# ETHERNET.net
KiCad netlist of a schematic drawn in Altium Designer
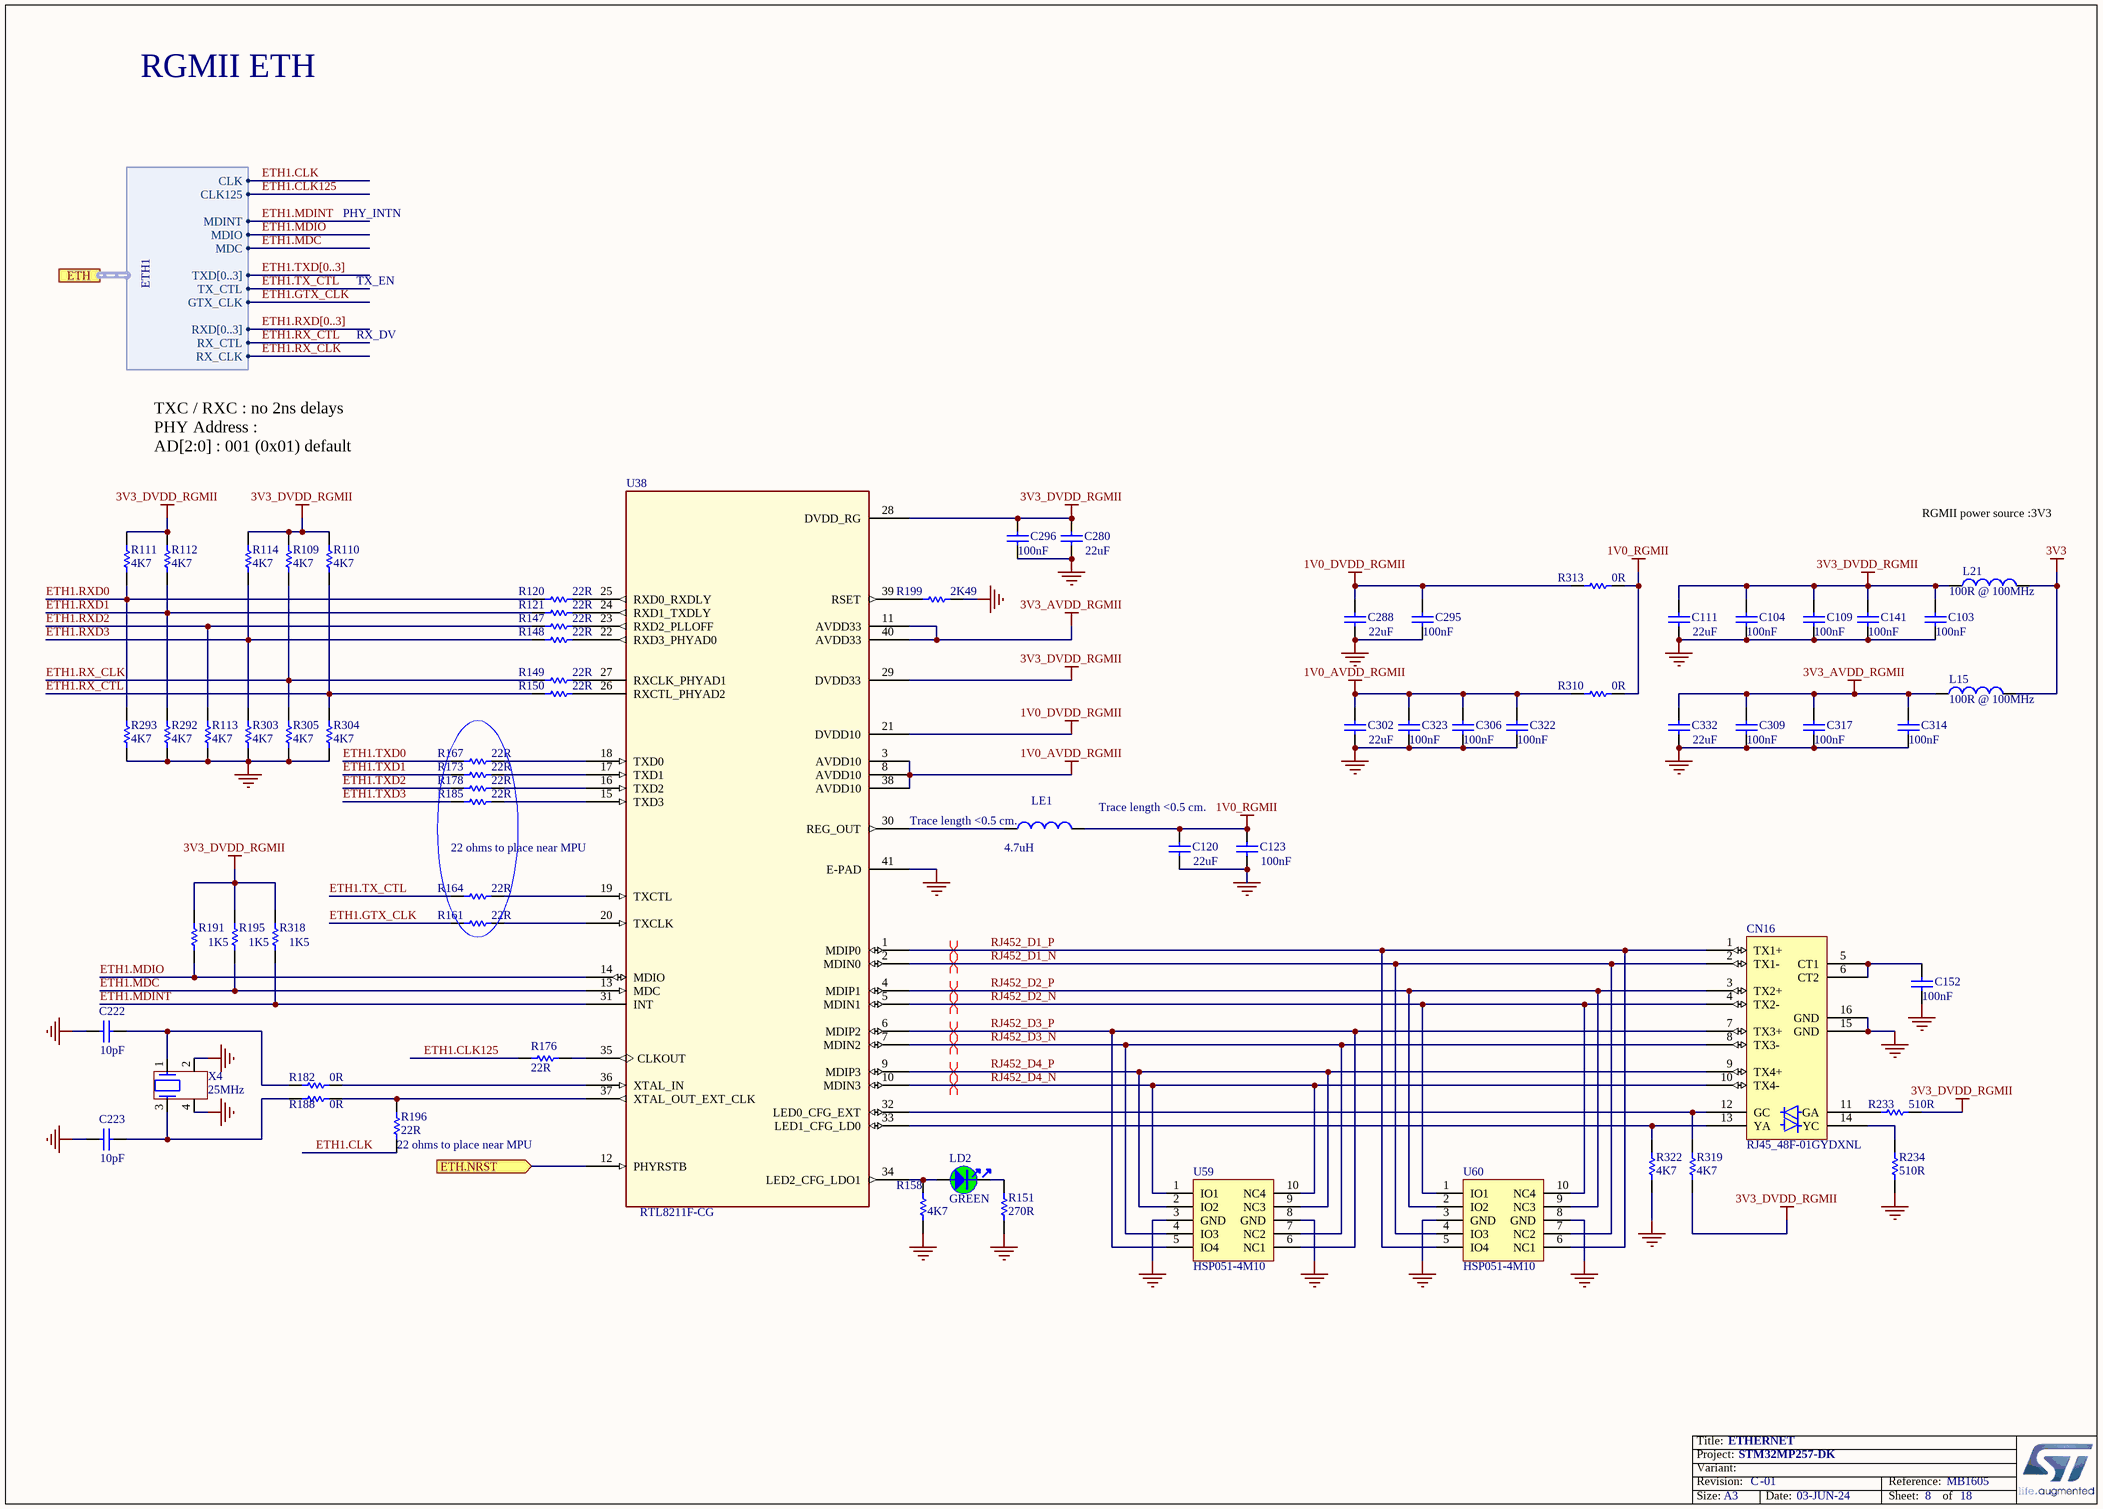
[diagram p0: ETHERNET.SchDoc]

(export (version "E")
  (design (tool "Eeschema 10.0.6"))
  (components
    (comp (ref "C103")
      (value "100nF")
      (footprint "C0402")
      (description "Capacitor,100nF,16V,X7R,10%,0402")
      (fields
        (field (name "INTERNAL_PART_NUMBER") "MCD-00006")
        (field (name "MANUFACTURER_PART_NUMBER") "CC0402KRX7R7BB104")
        (field (name "PROVIDED_BY") "SUBCO")
      )
      (libsource (lib "MCD_PARTS_database") (part "Capacitor"))
    )
    (comp (ref "C104")
      (value "100nF")
      (footprint "C0402")
      (description "Capacitor,100nF,16V,X7R,10%,0402")
      (fields
        (field (name "INTERNAL_PART_NUMBER") "MCD-00006")
        (field (name "MANUFACTURER_PART_NUMBER") "CC0402KRX7R7BB104")
        (field (name "PROVIDED_BY") "SUBCO")
      )
      (libsource (lib "MCD_PARTS_database") (part "Capacitor"))
    )
    (comp (ref "C109")
      (value "100nF")
      (footprint "C0402")
      (description "Capacitor,100nF,16V,X7R,10%,0402")
      (fields
        (field (name "INTERNAL_PART_NUMBER") "MCD-00006")
        (field (name "MANUFACTURER_PART_NUMBER") "CC0402KRX7R7BB104")
        (field (name "PROVIDED_BY") "SUBCO")
      )
      (libsource (lib "MCD_PARTS_database") (part "Capacitor"))
    )
    (comp (ref "C111")
      (value "22uF")
      (footprint "C0603")
      (description "Capacitor,22uF,6V3,X5R,20%,0603")
      (fields
        (field (name "INTERNAL_PART_NUMBER") "MCD-00100")
        (field (name "MANUFACTURER_PART_NUMBER") "GRM188R60J226MEA0J")
        (field (name "PROVIDED_BY") "SUBCO")
      )
      (libsource (lib "MCD_PARTS_database") (part "Capacitor"))
    )
    (comp (ref "C120")
      (value "22uF")
      (footprint "C0603")
      (description "Capacitor,22uF,6V3,X5R,20%,0603")
      (fields
        (field (name "INTERNAL_PART_NUMBER") "MCD-00100")
        (field (name "MANUFACTURER_PART_NUMBER") "GRM188R60J226MEA0J")
        (field (name "PROVIDED_BY") "SUBCO")
      )
      (libsource (lib "MCD_PARTS_database") (part "Capacitor"))
    )
    (comp (ref "C123")
      (value "100nF")
      (footprint "C0402")
      (description "Capacitor,100nF,16V,X7R,10%,0402")
      (fields
        (field (name "INTERNAL_PART_NUMBER") "MCD-00006")
        (field (name "MANUFACTURER_PART_NUMBER") "CC0402KRX7R7BB104")
        (field (name "PROVIDED_BY") "SUBCO")
      )
      (libsource (lib "MCD_PARTS_database") (part "Capacitor"))
    )
    (comp (ref "C141")
      (value "100nF")
      (footprint "C0402")
      (description "Capacitor,100nF,16V,X7R,10%,0402")
      (fields
        (field (name "INTERNAL_PART_NUMBER") "MCD-00006")
        (field (name "MANUFACTURER_PART_NUMBER") "CC0402KRX7R7BB104")
        (field (name "PROVIDED_BY") "SUBCO")
      )
      (libsource (lib "MCD_PARTS_database") (part "Capacitor"))
    )
    (comp (ref "C152")
      (value "100nF")
      (footprint "C0402")
      (description "Capacitor,100nF,16V,X7R,10%,0402")
      (fields
        (field (name "INTERNAL_PART_NUMBER") "MCD-00006")
        (field (name "MANUFACTURER_PART_NUMBER") "CC0402KRX7R7BB104")
        (field (name "PROVIDED_BY") "SUBCO")
      )
      (libsource (lib "MCD_PARTS_database") (part "Capacitor"))
    )
    (comp (ref "C222")
      (value "10pF")
      (footprint "C0402")
      (description "Capacitor,10pF,50V,NPO,5%,0402")
      (fields
        (field (name "INTERNAL_PART_NUMBER") "MCD-00015")
        (field (name "MANUFACTURER_PART_NUMBER") "CC0402JRNPO9BN100")
        (field (name "PROVIDED_BY") "SUBCO")
      )
      (libsource (lib "MCD_PARTS_database") (part "Capacitor"))
    )
    (comp (ref "C223")
      (value "10pF")
      (footprint "C0402")
      (description "Capacitor,10pF,50V,NPO,5%,0402")
      (fields
        (field (name "INTERNAL_PART_NUMBER") "MCD-00015")
        (field (name "MANUFACTURER_PART_NUMBER") "CC0402JRNPO9BN100")
        (field (name "PROVIDED_BY") "SUBCO")
      )
      (libsource (lib "MCD_PARTS_database") (part "Capacitor"))
    )
    (comp (ref "C280")
      (value "22uF")
      (footprint "C0603")
      (description "Capacitor,22uF,6V3,X5R,20%,0603")
      (fields
        (field (name "INTERNAL_PART_NUMBER") "MCD-00100")
        (field (name "MANUFACTURER_PART_NUMBER") "GRM188R60J226MEA0J")
        (field (name "PROVIDED_BY") "SUBCO")
      )
      (libsource (lib "MCD_PARTS_database") (part "Capacitor"))
    )
    (comp (ref "C288")
      (value "22uF")
      (footprint "C0603")
      (description "Capacitor,22uF,6V3,X5R,20%,0603")
      (fields
        (field (name "INTERNAL_PART_NUMBER") "MCD-00100")
        (field (name "MANUFACTURER_PART_NUMBER") "GRM188R60J226MEA0J")
        (field (name "PROVIDED_BY") "SUBCO")
      )
      (libsource (lib "MCD_PARTS_database") (part "Capacitor"))
    )
    (comp (ref "C295")
      (value "100nF")
      (footprint "C0402")
      (description "Capacitor,100nF,16V,X7R,10%,0402")
      (fields
        (field (name "INTERNAL_PART_NUMBER") "MCD-00006")
        (field (name "MANUFACTURER_PART_NUMBER") "CC0402KRX7R7BB104")
        (field (name "PROVIDED_BY") "SUBCO")
      )
      (libsource (lib "MCD_PARTS_database") (part "Capacitor"))
    )
    (comp (ref "C296")
      (value "100nF")
      (footprint "C0402")
      (description "Capacitor,100nF,16V,X7R,10%,0402")
      (fields
        (field (name "INTERNAL_PART_NUMBER") "MCD-00006")
        (field (name "MANUFACTURER_PART_NUMBER") "CC0402KRX7R7BB104")
        (field (name "PROVIDED_BY") "SUBCO")
      )
      (libsource (lib "MCD_PARTS_database") (part "Capacitor"))
    )
    (comp (ref "C302")
      (value "22uF")
      (footprint "C0603")
      (description "Capacitor,22uF,6V3,X5R,20%,0603")
      (fields
        (field (name "INTERNAL_PART_NUMBER") "MCD-00100")
        (field (name "MANUFACTURER_PART_NUMBER") "GRM188R60J226MEA0J")
        (field (name "PROVIDED_BY") "SUBCO")
      )
      (libsource (lib "MCD_PARTS_database") (part "Capacitor"))
    )
    (comp (ref "C306")
      (value "100nF")
      (footprint "C0402")
      (description "Capacitor,100nF,16V,X7R,10%,0402")
      (fields
        (field (name "INTERNAL_PART_NUMBER") "MCD-00006")
        (field (name "MANUFACTURER_PART_NUMBER") "CC0402KRX7R7BB104")
        (field (name "PROVIDED_BY") "SUBCO")
      )
      (libsource (lib "MCD_PARTS_database") (part "Capacitor"))
    )
    (comp (ref "C309")
      (value "100nF")
      (footprint "C0402")
      (description "Capacitor,100nF,16V,X7R,10%,0402")
      (fields
        (field (name "INTERNAL_PART_NUMBER") "MCD-00006")
        (field (name "MANUFACTURER_PART_NUMBER") "CC0402KRX7R7BB104")
        (field (name "PROVIDED_BY") "SUBCO")
      )
      (libsource (lib "MCD_PARTS_database") (part "Capacitor"))
    )
    (comp (ref "C314")
      (value "100nF")
      (footprint "C0402")
      (description "Capacitor,100nF,16V,X7R,10%,0402")
      (fields
        (field (name "INTERNAL_PART_NUMBER") "MCD-00006")
        (field (name "MANUFACTURER_PART_NUMBER") "CC0402KRX7R7BB104")
        (field (name "PROVIDED_BY") "SUBCO")
      )
      (libsource (lib "MCD_PARTS_database") (part "Capacitor"))
    )
    (comp (ref "C317")
      (value "100nF")
      (footprint "C0402")
      (description "Capacitor,100nF,16V,X7R,10%,0402")
      (fields
        (field (name "INTERNAL_PART_NUMBER") "MCD-00006")
        (field (name "MANUFACTURER_PART_NUMBER") "CC0402KRX7R7BB104")
        (field (name "PROVIDED_BY") "SUBCO")
      )
      (libsource (lib "MCD_PARTS_database") (part "Capacitor"))
    )
    (comp (ref "C322")
      (value "100nF")
      (footprint "C0402")
      (description "Capacitor,100nF,16V,X7R,10%,0402")
      (fields
        (field (name "INTERNAL_PART_NUMBER") "MCD-00006")
        (field (name "MANUFACTURER_PART_NUMBER") "CC0402KRX7R7BB104")
        (field (name "PROVIDED_BY") "SUBCO")
      )
      (libsource (lib "MCD_PARTS_database") (part "Capacitor"))
    )
    (comp (ref "C323")
      (value "100nF")
      (footprint "C0402")
      (description "Capacitor,100nF,16V,X7R,10%,0402")
      (fields
        (field (name "INTERNAL_PART_NUMBER") "MCD-00006")
        (field (name "MANUFACTURER_PART_NUMBER") "CC0402KRX7R7BB104")
        (field (name "PROVIDED_BY") "SUBCO")
      )
      (libsource (lib "MCD_PARTS_database") (part "Capacitor"))
    )
    (comp (ref "C332")
      (value "22uF")
      (footprint "C0603")
      (description "Capacitor,22uF,6V3,X5R,20%,0603")
      (fields
        (field (name "INTERNAL_PART_NUMBER") "MCD-00100")
        (field (name "MANUFACTURER_PART_NUMBER") "GRM188R60J226MEA0J")
        (field (name "PROVIDED_BY") "SUBCO")
      )
      (libsource (lib "MCD_PARTS_database") (part "Capacitor"))
    )
    (comp (ref "CN16")
      (value "RJ45_48F-01GYDXNL")
      (footprint "CON_RJ45_YD_48F-01GYDXNL_LED-P")
      (description "Connector_RJ45, led pull down, T= 13.84mm")
      (fields
        (field (name "INTERNAL_PART_NUMBER") "MCD-01129")
        (field (name "MANUFACTURER_PART_NUMBER") "48F-01GYDXNL")
      )
      (libsource (lib "MCD_PARTS_database") (part "RJ45_48F_01GYDXNL_LPD"))
    )
    (comp (ref "L15")
      (value "100R @ 100MHz")
      (footprint "FIL_0603_H0P65")
      (description "Ferrite bead 100R 2A 0603")
      (fields
        (field (name "INTERNAL_PART_NUMBER") "MCD-00094")
        (field (name "MANUFACTURER_PART_NUMBER") "BLM18EG101TN1")
        (field (name "PROVIDED_BY") "SUBCO")
      )
      (libsource (lib "MCD_PARTS_database") (part "BEAD"))
    )
    (comp (ref "L21")
      (value "100R @ 100MHz")
      (footprint "FIL_0603_H0P65")
      (description "Ferrite bead 100R 2A 0603")
      (fields
        (field (name "INTERNAL_PART_NUMBER") "MCD-00094")
        (field (name "MANUFACTURER_PART_NUMBER") "BLM18EG101TN1")
        (field (name "PROVIDED_BY") "SUBCO")
      )
      (libsource (lib "MCD_PARTS_database") (part "BEAD"))
    )
    (comp (ref "LD2")
      (value "GREEN")
      (footprint "LED_0603_OSRAM_LG-Q396-PS-35_GREEN_1A2K_H0P4")
      (description "LED Green, 0603 SMD, Forward Voltage Typ=2V, Max=2.5V")
      (fields
        (field (name "INTERNAL_PART_NUMBER") "MCD-00588")
        (field (name "MANUFACTURER_PART_NUMBER") "LG Q396-PS-35")
        (field (name "PROVIDED_BY") "SUBCO")
      )
      (libsource (lib "MCD_PARTS_database") (part "LED_green"))
    )
    (comp (ref "LE1")
      (value "4.7uH")
      (footprint "L1210_LQH")
      (description "FIXED IND 4.7UH 1A 180 MOHM 30% SMD")
      (fields
        (field (name "INTERNAL_PART_NUMBER") "MCD-00048")
        (field (name "MANUFACTURER_PART_NUMBER") "LQH32PN4R7NN0L")
        (field (name "PROVIDED_BY") "SUBCO")
      )
      (libsource (lib "MCD_PARTS_database") (part "Inductor"))
    )
    (comp (ref "R109")
      (value "4K7")
      (footprint "R0402")
      (description "Resistor,4K7,0402,1%,1/16W")
      (fields
        (field (name "INTERNAL_PART_NUMBER") "MCD-00065")
        (field (name "MANUFACTURER_PART_NUMBER") "RC0402FR-074K7L")
        (field (name "PROVIDED_BY") "SUBCO")
      )
      (libsource (lib "MCD_PARTS_database") (part "Resistor"))
    )
    (comp (ref "R110")
      (value "4K7")
      (footprint "R0402")
      (description "Resistor,4K7,0402,1%,1/16W")
      (fields
        (field (name "INTERNAL_PART_NUMBER") "MCD-00065")
        (field (name "MANUFACTURER_PART_NUMBER") "RC0402FR-074K7L")
        (field (name "PROVIDED_BY") "SUBCO")
      )
      (libsource (lib "MCD_PARTS_database") (part "Resistor"))
    )
    (comp (ref "R111")
      (value "4K7")
      (footprint "R0402")
      (description "Resistor,4K7,0402,1%,1/16W")
      (fields
        (field (name "INTERNAL_PART_NUMBER") "MCD-00065")
        (field (name "MANUFACTURER_PART_NUMBER") "RC0402FR-074K7L")
        (field (name "PROVIDED_BY") "SUBCO")
      )
      (libsource (lib "MCD_PARTS_database") (part "Resistor"))
    )
    (comp (ref "R112")
      (value "4K7")
      (footprint "R0402")
      (description "Resistor,4K7,0402,1%,1/16W")
      (fields
        (field (name "INTERNAL_PART_NUMBER") "MCD-00065")
        (field (name "MANUFACTURER_PART_NUMBER") "RC0402FR-074K7L")
        (field (name "PROVIDED_BY") "SUBCO")
      )
      (libsource (lib "MCD_PARTS_database") (part "Resistor"))
    )
    (comp (ref "R113")
      (value "4K7")
      (footprint "R0402")
      (description "Resistor,4K7,0402,1%,1/16W")
      (fields
        (field (name "INTERNAL_PART_NUMBER") "MCD-00065")
        (field (name "MANUFACTURER_PART_NUMBER") "RC0402FR-074K7L")
        (field (name "PROVIDED_BY") "SUBCO")
      )
      (libsource (lib "MCD_PARTS_database") (part "Resistor"))
    )
    (comp (ref "R114")
      (value "4K7")
      (footprint "R0402")
      (description "Resistor,4K7,0402,1%,1/16W")
      (fields
        (field (name "INTERNAL_PART_NUMBER") "MCD-00065")
        (field (name "MANUFACTURER_PART_NUMBER") "RC0402FR-074K7L")
        (field (name "PROVIDED_BY") "SUBCO")
      )
      (libsource (lib "MCD_PARTS_database") (part "Resistor"))
    )
    (comp (ref "R120")
      (value "22R")
      (footprint "R0201_H0P23")
      (description "Resistor, 22R, 0201, +/-1%, 1/20W")
      (fields
        (field (name "INTERNAL_PART_NUMBER") "MCD-02978")
        (field (name "MANUFACTURER_PART_NUMBER") "RC0201FR-0722RL")
      )
      (libsource (lib "MCD_PARTS_database") (part "Resistor"))
    )
    (comp (ref "R121")
      (value "22R")
      (footprint "R0201_H0P23")
      (description "Resistor, 22R, 0201, +/-1%, 1/20W")
      (fields
        (field (name "INTERNAL_PART_NUMBER") "MCD-02978")
        (field (name "MANUFACTURER_PART_NUMBER") "RC0201FR-0722RL")
      )
      (libsource (lib "MCD_PARTS_database") (part "Resistor"))
    )
    (comp (ref "R147")
      (value "22R")
      (footprint "R0201_H0P23")
      (description "Resistor, 22R, 0201, +/-1%, 1/20W")
      (fields
        (field (name "INTERNAL_PART_NUMBER") "MCD-02978")
        (field (name "MANUFACTURER_PART_NUMBER") "RC0201FR-0722RL")
      )
      (libsource (lib "MCD_PARTS_database") (part "Resistor"))
    )
    (comp (ref "R148")
      (value "22R")
      (footprint "R0201_H0P23")
      (description "Resistor, 22R, 0201, +/-1%, 1/20W")
      (fields
        (field (name "INTERNAL_PART_NUMBER") "MCD-02978")
        (field (name "MANUFACTURER_PART_NUMBER") "RC0201FR-0722RL")
      )
      (libsource (lib "MCD_PARTS_database") (part "Resistor"))
    )
    (comp (ref "R149")
      (value "22R")
      (footprint "R0201_H0P23")
      (description "Resistor, 22R, 0201, +/-1%, 1/20W")
      (fields
        (field (name "INTERNAL_PART_NUMBER") "MCD-02978")
        (field (name "MANUFACTURER_PART_NUMBER") "RC0201FR-0722RL")
      )
      (libsource (lib "MCD_PARTS_database") (part "Resistor"))
    )
    (comp (ref "R150")
      (value "22R")
      (footprint "R0201_H0P23")
      (description "Resistor, 22R, 0201, +/-1%, 1/20W")
      (fields
        (field (name "INTERNAL_PART_NUMBER") "MCD-02978")
        (field (name "MANUFACTURER_PART_NUMBER") "RC0201FR-0722RL")
      )
      (libsource (lib "MCD_PARTS_database") (part "Resistor"))
    )
    (comp (ref "R151")
      (value "270R")
      (footprint "R0402")
      (description "Resistor,270R,0402,1%,1/16W")
      (fields
        (field (name "INTERNAL_PART_NUMBER") "MCD-00441")
        (field (name "MANUFACTURER_PART_NUMBER") "RC0402FR-07270RL")
        (field (name "PROVIDED_BY") "SUBCO")
      )
      (libsource (lib "MCD_PARTS_database") (part "Resistor"))
    )
    (comp (ref "R158")
      (value "4K7")
      (footprint "R0402")
      (description "Resistor,4K7,0402,1%,1/16W")
      (fields
        (field (name "INTERNAL_PART_NUMBER") "MCD-00065")
        (field (name "MANUFACTURER_PART_NUMBER") "RC0402FR-074K7L")
        (field (name "PROVIDED_BY") "SUBCO")
      )
      (libsource (lib "MCD_PARTS_database") (part "Resistor"))
    )
    (comp (ref "R161")
      (value "22R")
      (footprint "R0201_H0P23")
      (description "Resistor, 22R, 0201, +/-1%, 1/20W")
      (fields
        (field (name "INTERNAL_PART_NUMBER") "MCD-02978")
        (field (name "MANUFACTURER_PART_NUMBER") "RC0201FR-0722RL")
      )
      (libsource (lib "MCD_PARTS_database") (part "Resistor"))
    )
    (comp (ref "R164")
      (value "22R")
      (footprint "R0201_H0P23")
      (description "Resistor, 22R, 0201, +/-1%, 1/20W")
      (fields
        (field (name "INTERNAL_PART_NUMBER") "MCD-02978")
        (field (name "MANUFACTURER_PART_NUMBER") "RC0201FR-0722RL")
      )
      (libsource (lib "MCD_PARTS_database") (part "Resistor"))
    )
    (comp (ref "R167")
      (value "22R")
      (footprint "R0201_H0P23")
      (description "Resistor, 22R, 0201, +/-1%, 1/20W")
      (fields
        (field (name "INTERNAL_PART_NUMBER") "MCD-02978")
        (field (name "MANUFACTURER_PART_NUMBER") "RC0201FR-0722RL")
      )
      (libsource (lib "MCD_PARTS_database") (part "Resistor"))
    )
    (comp (ref "R173")
      (value "22R")
      (footprint "R0201_H0P23")
      (description "Resistor, 22R, 0201, +/-1%, 1/20W")
      (fields
        (field (name "INTERNAL_PART_NUMBER") "MCD-02978")
        (field (name "MANUFACTURER_PART_NUMBER") "RC0201FR-0722RL")
      )
      (libsource (lib "MCD_PARTS_database") (part "Resistor"))
    )
    (comp (ref "R176")
      (value "22R")
      (footprint "R0201_H0P23")
      (description "Resistor, 22R, 0201, +/-1%, 1/20W")
      (fields
        (field (name "INTERNAL_PART_NUMBER") "MCD-02978")
        (field (name "MANUFACTURER_PART_NUMBER") "RC0201FR-0722RL")
      )
      (libsource (lib "MCD_PARTS_database") (part "Resistor"))
    )
    (comp (ref "R178")
      (value "22R")
      (footprint "R0201_H0P23")
      (description "Resistor, 22R, 0201, +/-1%, 1/20W")
      (fields
        (field (name "INTERNAL_PART_NUMBER") "MCD-02978")
        (field (name "MANUFACTURER_PART_NUMBER") "RC0201FR-0722RL")
      )
      (libsource (lib "MCD_PARTS_database") (part "Resistor"))
    )
    (comp (ref "R182")
      (value "0R")
      (footprint "R0402")
      (description "Resistor,0R,0402,5%,1/16W")
      (fields
        (field (name "INTERNAL_PART_NUMBER") "MCD-00052")
        (field (name "MANUFACTURER_PART_NUMBER") "RC0402JR-070RL")
        (field (name "PROVIDED_BY") "SUBCO")
      )
      (libsource (lib "MCD_PARTS_database") (part "Resistor"))
    )
    (comp (ref "R185")
      (value "22R")
      (footprint "R0201_H0P23")
      (description "Resistor, 22R, 0201, +/-1%, 1/20W")
      (fields
        (field (name "INTERNAL_PART_NUMBER") "MCD-02978")
        (field (name "MANUFACTURER_PART_NUMBER") "RC0201FR-0722RL")
      )
      (libsource (lib "MCD_PARTS_database") (part "Resistor"))
    )
    (comp (ref "R188")
      (value "0R")
      (footprint "R0402")
      (description "Resistor,0R,0402,5%,1/16W")
      (fields
        (field (name "INTERNAL_PART_NUMBER") "MCD-00052")
        (field (name "MANUFACTURER_PART_NUMBER") "RC0402JR-070RL")
        (field (name "PROVIDED_BY") "SUBCO")
      )
      (libsource (lib "MCD_PARTS_database") (part "Resistor"))
    )
    (comp (ref "R191")
      (value "1K5")
      (footprint "R0402")
      (description "Resistor,1K5,0402,1%,1/16W")
      (fields
        (field (name "INTERNAL_PART_NUMBER") "MCD-00068")
        (field (name "MANUFACTURER_PART_NUMBER") "RC0402FR-071K5L")
        (field (name "PROVIDED_BY") "SUBCO")
      )
      (libsource (lib "MCD_PARTS_database") (part "Resistor"))
    )
    (comp (ref "R195")
      (value "1K5")
      (footprint "R0402")
      (description "Resistor,1K5,0402,1%,1/16W")
      (fields
        (field (name "INTERNAL_PART_NUMBER") "MCD-00068")
        (field (name "MANUFACTURER_PART_NUMBER") "RC0402FR-071K5L")
        (field (name "PROVIDED_BY") "SUBCO")
      )
      (libsource (lib "MCD_PARTS_database") (part "Resistor"))
    )
    (comp (ref "R196")
      (value "22R")
      (footprint "R0201_H0P23")
      (description "Resistor, 22R, 0201, +/-1%, 1/20W")
      (fields
        (field (name "INTERNAL_PART_NUMBER") "MCD-02978")
        (field (name "MANUFACTURER_PART_NUMBER") "RC0201FR-0722RL")
      )
      (libsource (lib "MCD_PARTS_database") (part "Resistor"))
    )
    (comp (ref "R199")
      (value "2K49")
      (footprint "R0402")
      (description "Resistor,2K49,0402,1%,1/16W")
      (fields
        (field (name "INTERNAL_PART_NUMBER") "MCD-00183")
        (field (name "MANUFACTURER_PART_NUMBER") "RC0402FR-072K49L")
        (field (name "PROVIDED_BY") "SUBCO")
      )
      (libsource (lib "MCD_PARTS_database") (part "Resistor"))
    )
    (comp (ref "R233")
      (value "510R")
      (footprint "R0402")
      (description "Resistor,510R,0402,1%,1/16W")
      (fields
        (field (name "INTERNAL_PART_NUMBER") "MCD-00064")
        (field (name "MANUFACTURER_PART_NUMBER") "RC0402FR-07510RL")
        (field (name "PROVIDED_BY") "SUBCO")
      )
      (libsource (lib "MCD_PARTS_database") (part "Resistor"))
    )
    (comp (ref "R234")
      (value "510R")
      (footprint "R0402")
      (description "Resistor,510R,0402,1%,1/16W")
      (fields
        (field (name "INTERNAL_PART_NUMBER") "MCD-00064")
        (field (name "MANUFACTURER_PART_NUMBER") "RC0402FR-07510RL")
        (field (name "PROVIDED_BY") "SUBCO")
      )
      (libsource (lib "MCD_PARTS_database") (part "Resistor"))
    )
    (comp (ref "R292")
      (value "4K7")
      (footprint "R0402")
      (description "Resistor,4K7,0402,1%,1/16W")
      (fields
        (field (name "INTERNAL_PART_NUMBER") "MCD-00065")
        (field (name "MANUFACTURER_PART_NUMBER") "RC0402FR-074K7L")
        (field (name "PROVIDED_BY") "SUBCO")
      )
      (libsource (lib "MCD_PARTS_database") (part "Resistor"))
    )
    (comp (ref "R293")
      (value "4K7")
      (footprint "R0402")
      (description "Resistor,4K7,0402,1%,1/16W")
      (fields
        (field (name "INTERNAL_PART_NUMBER") "MCD-00065")
        (field (name "MANUFACTURER_PART_NUMBER") "RC0402FR-074K7L")
        (field (name "PROVIDED_BY") "SUBCO")
      )
      (libsource (lib "MCD_PARTS_database") (part "Resistor"))
    )
    (comp (ref "R303")
      (value "4K7")
      (footprint "R0402")
      (description "Resistor,4K7,0402,1%,1/16W")
      (fields
        (field (name "INTERNAL_PART_NUMBER") "MCD-00065")
        (field (name "MANUFACTURER_PART_NUMBER") "RC0402FR-074K7L")
        (field (name "PROVIDED_BY") "SUBCO")
      )
      (libsource (lib "MCD_PARTS_database") (part "Resistor"))
    )
    (comp (ref "R304")
      (value "4K7")
      (footprint "R0402")
      (description "Resistor,4K7,0402,1%,1/16W")
      (fields
        (field (name "INTERNAL_PART_NUMBER") "MCD-00065")
        (field (name "MANUFACTURER_PART_NUMBER") "RC0402FR-074K7L")
        (field (name "PROVIDED_BY") "SUBCO")
      )
      (libsource (lib "MCD_PARTS_database") (part "Resistor"))
    )
    (comp (ref "R305")
      (value "4K7")
      (footprint "R0402")
      (description "Resistor,4K7,0402,1%,1/16W")
      (fields
        (field (name "INTERNAL_PART_NUMBER") "MCD-00065")
        (field (name "MANUFACTURER_PART_NUMBER") "RC0402FR-074K7L")
        (field (name "PROVIDED_BY") "SUBCO")
      )
      (libsource (lib "MCD_PARTS_database") (part "Resistor"))
    )
    (comp (ref "R310")
      (value "0R")
      (footprint "R0603")
      (description "Resistor,0R,0603,5%,1/10W")
      (fields
        (field (name "INTERNAL_PART_NUMBER") "MCD-00056")
        (field (name "MANUFACTURER_PART_NUMBER") "RC0603JR-070RL")
        (field (name "PROVIDED_BY") "SUBCO")
      )
      (libsource (lib "MCD_PARTS_database") (part "Resistor"))
    )
    (comp (ref "R313")
      (value "0R")
      (footprint "R0603")
      (description "Resistor,0R,0603,5%,1/10W")
      (fields
        (field (name "INTERNAL_PART_NUMBER") "MCD-00056")
        (field (name "MANUFACTURER_PART_NUMBER") "RC0603JR-070RL")
        (field (name "PROVIDED_BY") "SUBCO")
      )
      (libsource (lib "MCD_PARTS_database") (part "Resistor"))
    )
    (comp (ref "R318")
      (value "1K5")
      (footprint "R0402")
      (description "Resistor,1K5,0402,1%,1/16W")
      (fields
        (field (name "INTERNAL_PART_NUMBER") "MCD-00068")
        (field (name "MANUFACTURER_PART_NUMBER") "RC0402FR-071K5L")
        (field (name "PROVIDED_BY") "SUBCO")
      )
      (libsource (lib "MCD_PARTS_database") (part "Resistor"))
    )
    (comp (ref "R319")
      (value "4K7")
      (footprint "R0402")
      (description "Resistor,4K7,0402,1%,1/16W")
      (fields
        (field (name "INTERNAL_PART_NUMBER") "MCD-00065")
        (field (name "MANUFACTURER_PART_NUMBER") "RC0402FR-074K7L")
        (field (name "PROVIDED_BY") "SUBCO")
      )
      (libsource (lib "MCD_PARTS_database") (part "Resistor"))
    )
    (comp (ref "R322")
      (value "4K7")
      (footprint "R0402")
      (description "Resistor,4K7,0402,1%,1/16W")
      (fields
        (field (name "INTERNAL_PART_NUMBER") "MCD-00065")
        (field (name "MANUFACTURER_PART_NUMBER") "RC0402FR-074K7L")
        (field (name "PROVIDED_BY") "SUBCO")
      )
      (libsource (lib "MCD_PARTS_database") (part "Resistor"))
    )
    (comp (ref "U38")
      (value "RTL8211F-CG")
      (footprint "ICC_QFN40-EPAD_5X5_P040")
      (description "10/100/1000M GIGABIT Ethernet Transceiver, QFN40 , SMPS version")
      (fields
        (field (name "INTERNAL_PART_NUMBER") "MCD-01130")
        (field (name "MANUFACTURER") "REALTEK")
        (field (name "PROVIDED_BY") "SUBCO")
      )
      (libsource (lib "MCD_PARTS_database") (part "RTL8211F-CG"))
    )
    (comp (ref "U59")
      (value "HSP051-4M10")
      (footprint "ESD_UQFN-10L_2P5X1_P050")
      (description "4-line ESD protection for high speed lines")
      (fields (field (name "INTERNAL_PART_NUMBER") "MCD-00667") (field (name "BMS_PART_NUMBER") "9179041"))
      (libsource (lib "MCD_PARTS_database") (part "HSP051-4M10"))
    )
    (comp (ref "U60")
      (value "HSP051-4M10")
      (footprint "ESD_UQFN-10L_2P5X1_P050")
      (description "4-line ESD protection for high speed lines")
      (fields (field (name "INTERNAL_PART_NUMBER") "MCD-00667") (field (name "BMS_PART_NUMBER") "9179041"))
      (libsource (lib "MCD_PARTS_database") (part "HSP051-4M10"))
    )
    (comp (ref "X4")
      (value "25MHz")
      (footprint "CRY_NX3225HA_4P")
      (description "Crystal 25Mhz, 10pF, -+50PPM, SMD")
      (fields
        (field (name "INTERNAL_PART_NUMBER") "MCD-01463")
        (field (name "MANUFACTURER_PART_NUMBER") "NX3225GA-25MHZ-EXS00A-CG06750")
        (field (name "PROVIDED_BY") "SUBCO")
      )
      (libsource (lib "MCD_PARTS_database") (part "XTAL_4_PINS"))
    )
  )
  (nets
    (net (code "2") (name "/ETH.NRST") (class "Default")
      (node (ref "U38") (pin "12") (pinfunction "PHYRSTB_12") (pintype "input"))
    )
    (net (code "3") (name "/ETH1.CLK") (class "Default")
      (node (ref "R196") (pin "1") (pinfunction "1_1") (pintype "passive"))
    )
    (net (code "4") (name "/ETH1.CLK125") (class "Default")
      (node (ref "R176") (pin "1") (pinfunction "1_1") (pintype "passive"))
    )
    (net (code "5") (name "/ETH1.GTX_CLK") (class "Default")
      (node (ref "R161") (pin "1") (pinfunction "1_1") (pintype "passive"))
    )
    (net (code "6") (name "/ETH1.MDC") (class "Default")
      (node (ref "R195") (pin "1") (pinfunction "1_1") (pintype "passive"))
      (node (ref "U38") (pin "13") (pinfunction "MDC_13") (pintype "input"))
    )
    (net (code "7") (name "/ETH1.MDINT") (class "Default")
      (node (ref "R318") (pin "1") (pinfunction "1_1") (pintype "passive"))
      (node (ref "U38") (pin "31") (pinfunction "INT_31") (pintype "passive"))
    )
    (net (code "8") (name "/ETH1.MDIO") (class "Default")
      (node (ref "R191") (pin "1") (pinfunction "1_1") (pintype "passive"))
      (node (ref "U38") (pin "14") (pinfunction "MDIO_14") (pintype "bidirectional"))
    )
    (net (code "9") (name "/ETH1.RXD0") (class "Default")
      (node (ref "R111") (pin "1") (pinfunction "1_1") (pintype "passive"))
      (node (ref "R120") (pin "1") (pinfunction "1_1") (pintype "passive"))
      (node (ref "R293") (pin "2") (pinfunction "2_2") (pintype "passive"))
    )
    (net (code "10") (name "/ETH1.RXD1") (class "Default")
      (node (ref "R112") (pin "1") (pinfunction "1_1") (pintype "passive"))
      (node (ref "R121") (pin "1") (pinfunction "1_1") (pintype "passive"))
      (node (ref "R292") (pin "2") (pinfunction "2_2") (pintype "passive"))
    )
    (net (code "11") (name "/ETH1.RXD2") (class "Default")
      (node (ref "R113") (pin "2") (pinfunction "2_2") (pintype "passive"))
      (node (ref "R147") (pin "1") (pinfunction "1_1") (pintype "passive"))
    )
    (net (code "12") (name "/ETH1.RXD3") (class "Default")
      (node (ref "R114") (pin "1") (pinfunction "1_1") (pintype "passive"))
      (node (ref "R148") (pin "1") (pinfunction "1_1") (pintype "passive"))
      (node (ref "R303") (pin "2") (pinfunction "2_2") (pintype "passive"))
    )
    (net (code "14") (name "/ETH1.RX_CLK") (class "Default")
      (node (ref "R109") (pin "1") (pinfunction "1_1") (pintype "passive"))
      (node (ref "R149") (pin "1") (pinfunction "1_1") (pintype "passive"))
      (node (ref "R305") (pin "2") (pinfunction "2_2") (pintype "passive"))
    )
    (net (code "15") (name "/ETH1.RX_CTL") (class "Default")
      (node (ref "R110") (pin "1") (pinfunction "1_1") (pintype "passive"))
      (node (ref "R150") (pin "1") (pinfunction "1_1") (pintype "passive"))
      (node (ref "R304") (pin "2") (pinfunction "2_2") (pintype "passive"))
    )
    (net (code "16") (name "/ETH1.TXD0") (class "Default")
      (node (ref "R167") (pin "1") (pinfunction "1_1") (pintype "passive"))
    )
    (net (code "17") (name "/ETH1.TXD1") (class "Default")
      (node (ref "R173") (pin "1") (pinfunction "1_1") (pintype "passive"))
    )
    (net (code "18") (name "/ETH1.TXD2") (class "Default")
      (node (ref "R178") (pin "1") (pinfunction "1_1") (pintype "passive"))
    )
    (net (code "19") (name "/ETH1.TXD3") (class "Default")
      (node (ref "R185") (pin "1") (pinfunction "1_1") (pintype "passive"))
    )
    (net (code "21") (name "/ETH1.TX_CTL") (class "Default")
      (node (ref "R164") (pin "1") (pinfunction "1_1") (pintype "passive"))
    )
    (net (code "22") (name "/RJ452_D1_N") (class "Default")
      (node (ref "CN16") (pin "2") (pinfunction "TX1-_2") (pintype "bidirectional"))
      (node (ref "U38") (pin "2") (pinfunction "MDIN0_2") (pintype "bidirectional"))
      (node (ref "U60") (pin "4") (pinfunction "IO3_4") (pintype "passive"))
      (node (ref "U60") (pin "7") (pinfunction "NC2_7") (pintype "passive"))
    )
    (net (code "23") (name "/RJ452_D1_P") (class "Default")
      (node (ref "CN16") (pin "1") (pinfunction "TX1+_1") (pintype "bidirectional"))
      (node (ref "U38") (pin "1") (pinfunction "MDIP0_1") (pintype "bidirectional"))
      (node (ref "U60") (pin "5") (pinfunction "IO4_5") (pintype "passive"))
      (node (ref "U60") (pin "6") (pinfunction "NC1_6") (pintype "passive"))
    )
    (net (code "24") (name "/RJ452_D2_N") (class "Default")
      (node (ref "CN16") (pin "4") (pinfunction "TX2-_4") (pintype "bidirectional"))
      (node (ref "U38") (pin "5") (pinfunction "MDIN1_5") (pintype "bidirectional"))
      (node (ref "U60") (pin "1") (pinfunction "IO1_1") (pintype "passive"))
      (node (ref "U60") (pin "10") (pinfunction "NC4_10") (pintype "passive"))
    )
    (net (code "25") (name "/RJ452_D2_P") (class "Default")
      (node (ref "CN16") (pin "3") (pinfunction "TX2+_3") (pintype "bidirectional"))
      (node (ref "U38") (pin "4") (pinfunction "MDIP1_4") (pintype "bidirectional"))
      (node (ref "U60") (pin "2") (pinfunction "IO2_2") (pintype "passive"))
      (node (ref "U60") (pin "9") (pinfunction "NC3_9") (pintype "passive"))
    )
    (net (code "26") (name "/RJ452_D3_N") (class "Default")
      (node (ref "CN16") (pin "8") (pinfunction "TX3-_8") (pintype "bidirectional"))
      (node (ref "U38") (pin "7") (pinfunction "MDIN2_7") (pintype "bidirectional"))
      (node (ref "U59") (pin "4") (pinfunction "IO3_4") (pintype "passive"))
      (node (ref "U59") (pin "7") (pinfunction "NC2_7") (pintype "passive"))
    )
    (net (code "27") (name "/RJ452_D3_P") (class "Default")
      (node (ref "CN16") (pin "7") (pinfunction "TX3+_7") (pintype "bidirectional"))
      (node (ref "U38") (pin "6") (pinfunction "MDIP2_6") (pintype "bidirectional"))
      (node (ref "U59") (pin "5") (pinfunction "IO4_5") (pintype "passive"))
      (node (ref "U59") (pin "6") (pinfunction "NC1_6") (pintype "passive"))
    )
    (net (code "28") (name "/RJ452_D4_N") (class "Default")
      (node (ref "CN16") (pin "10") (pinfunction "TX4-_10") (pintype "bidirectional"))
      (node (ref "U38") (pin "10") (pinfunction "MDIN3_10") (pintype "bidirectional"))
      (node (ref "U59") (pin "1") (pinfunction "IO1_1") (pintype "passive"))
      (node (ref "U59") (pin "10") (pinfunction "NC4_10") (pintype "passive"))
    )
    (net (code "29") (name "/RJ452_D4_P") (class "Default")
      (node (ref "CN16") (pin "9") (pinfunction "TX4+_9") (pintype "bidirectional"))
      (node (ref "U38") (pin "9") (pinfunction "MDIP3_9") (pintype "bidirectional"))
      (node (ref "U59") (pin "2") (pinfunction "IO2_2") (pintype "passive"))
      (node (ref "U59") (pin "9") (pinfunction "NC3_9") (pintype "passive"))
    )
    (net (code "31") (name "1V0_AVDD_RGMII") (class "Default")
      (node (ref "C302") (pin "2") (pinfunction "2_2") (pintype "passive"))
      (node (ref "C306") (pin "2") (pinfunction "2_2") (pintype "passive"))
      (node (ref "C322") (pin "2") (pinfunction "2_2") (pintype "passive"))
      (node (ref "C323") (pin "2") (pinfunction "2_2") (pintype "passive"))
      (node (ref "R310") (pin "1") (pinfunction "1_1") (pintype "passive"))
      (node (ref "U38") (pin "3") (pinfunction "AVDD10_3") (pintype "power_in"))
      (node (ref "U38") (pin "38") (pinfunction "AVDD10_38") (pintype "power_in"))
      (node (ref "U38") (pin "8") (pinfunction "AVDD10_8") (pintype "power_in"))
    )
    (net (code "32") (name "1V0_DVDD_RGMII") (class "Default")
      (node (ref "C288") (pin "2") (pinfunction "2_2") (pintype "passive"))
      (node (ref "C295") (pin "2") (pinfunction "2_2") (pintype "passive"))
      (node (ref "R313") (pin "1") (pinfunction "1_1") (pintype "passive"))
      (node (ref "U38") (pin "21") (pinfunction "DVDD10_21") (pintype "power_in"))
    )
    (net (code "33") (name "1V0_RGMII") (class "Default")
      (node (ref "C120") (pin "2") (pinfunction "2_2") (pintype "passive"))
      (node (ref "C123") (pin "2") (pinfunction "2_2") (pintype "passive"))
      (node (ref "LE1") (pin "2") (pinfunction "2_2") (pintype "passive"))
      (node (ref "R310") (pin "2") (pinfunction "2_2") (pintype "passive"))
      (node (ref "R313") (pin "2") (pinfunction "2_2") (pintype "passive"))
    )
    (net (code "34") (name "3V3") (class "Default")
      (node (ref "L15") (pin "2") (pinfunction "2_2") (pintype "passive"))
      (node (ref "L21") (pin "2") (pinfunction "2_2") (pintype "passive"))
    )
    (net (code "35") (name "3V3_AVDD_RGMII") (class "Default")
      (node (ref "C309") (pin "2") (pinfunction "2_2") (pintype "passive"))
      (node (ref "C314") (pin "2") (pinfunction "2_2") (pintype "passive"))
      (node (ref "C317") (pin "2") (pinfunction "2_2") (pintype "passive"))
      (node (ref "C332") (pin "2") (pinfunction "2_2") (pintype "passive"))
      (node (ref "L15") (pin "1") (pinfunction "1_1") (pintype "passive"))
      (node (ref "U38") (pin "11") (pinfunction "AVDD33_11") (pintype "power_in"))
      (node (ref "U38") (pin "40") (pinfunction "AVDD33_40") (pintype "power_in"))
    )
    (net (code "36") (name "3V3_DVDD_RGMII") (class "Default")
      (node (ref "C103") (pin "2") (pinfunction "2_2") (pintype "passive"))
      (node (ref "C104") (pin "2") (pinfunction "2_2") (pintype "passive"))
      (node (ref "C109") (pin "2") (pinfunction "2_2") (pintype "passive"))
      (node (ref "C111") (pin "2") (pinfunction "2_2") (pintype "passive"))
      (node (ref "C141") (pin "2") (pinfunction "2_2") (pintype "passive"))
      (node (ref "C280") (pin "1") (pinfunction "1_1") (pintype "passive"))
      (node (ref "C296") (pin "2") (pinfunction "2_2") (pintype "passive"))
      (node (ref "L21") (pin "1") (pinfunction "1_1") (pintype "passive"))
      (node (ref "R109") (pin "2") (pinfunction "2_2") (pintype "passive"))
      (node (ref "R110") (pin "2") (pinfunction "2_2") (pintype "passive"))
      (node (ref "R111") (pin "2") (pinfunction "2_2") (pintype "passive"))
      (node (ref "R112") (pin "2") (pinfunction "2_2") (pintype "passive"))
      (node (ref "R114") (pin "2") (pinfunction "2_2") (pintype "passive"))
      (node (ref "R191") (pin "2") (pinfunction "2_2") (pintype "passive"))
      (node (ref "R195") (pin "2") (pinfunction "2_2") (pintype "passive"))
      (node (ref "R233") (pin "2") (pinfunction "2_2") (pintype "passive"))
      (node (ref "R318") (pin "2") (pinfunction "2_2") (pintype "passive"))
      (node (ref "R319") (pin "1") (pinfunction "1_1") (pintype "passive"))
      (node (ref "U38") (pin "28") (pinfunction "DVDD_RG_28") (pintype "power_in"))
      (node (ref "U38") (pin "29") (pinfunction "DVDD33_29") (pintype "power_in"))
    )
    (net (code "37") (name "GND") (class "Default")
      (node (ref "C103") (pin "1") (pinfunction "1_1") (pintype "passive"))
      (node (ref "C104") (pin "1") (pinfunction "1_1") (pintype "passive"))
      (node (ref "C109") (pin "1") (pinfunction "1_1") (pintype "passive"))
      (node (ref "C111") (pin "1") (pinfunction "1_1") (pintype "passive"))
      (node (ref "C120") (pin "1") (pinfunction "1_1") (pintype "passive"))
      (node (ref "C123") (pin "1") (pinfunction "1_1") (pintype "passive"))
      (node (ref "C141") (pin "1") (pinfunction "1_1") (pintype "passive"))
      (node (ref "C152") (pin "1") (pinfunction "1_1") (pintype "passive"))
      (node (ref "C222") (pin "1") (pinfunction "1_1") (pintype "passive"))
      (node (ref "C223") (pin "1") (pinfunction "1_1") (pintype "passive"))
      (node (ref "C280") (pin "2") (pinfunction "2_2") (pintype "passive"))
      (node (ref "C288") (pin "1") (pinfunction "1_1") (pintype "passive"))
      (node (ref "C295") (pin "1") (pinfunction "1_1") (pintype "passive"))
      (node (ref "C296") (pin "1") (pinfunction "1_1") (pintype "passive"))
      (node (ref "C302") (pin "1") (pinfunction "1_1") (pintype "passive"))
      (node (ref "C306") (pin "1") (pinfunction "1_1") (pintype "passive"))
      (node (ref "C309") (pin "1") (pinfunction "1_1") (pintype "passive"))
      (node (ref "C314") (pin "1") (pinfunction "1_1") (pintype "passive"))
      (node (ref "C317") (pin "1") (pinfunction "1_1") (pintype "passive"))
      (node (ref "C322") (pin "1") (pinfunction "1_1") (pintype "passive"))
      (node (ref "C323") (pin "1") (pinfunction "1_1") (pintype "passive"))
      (node (ref "C332") (pin "1") (pinfunction "1_1") (pintype "passive"))
      (node (ref "CN16") (pin "15") (pinfunction "GND_15") (pintype "power_in"))
      (node (ref "CN16") (pin "16") (pinfunction "GND_16") (pintype "power_in"))
      (node (ref "R113") (pin "1") (pinfunction "1_1") (pintype "passive"))
      (node (ref "R151") (pin "2") (pinfunction "2_2") (pintype "passive"))
      (node (ref "R158") (pin "1") (pinfunction "1_1") (pintype "passive"))
      (node (ref "R199") (pin "2") (pinfunction "2_2") (pintype "passive"))
      (node (ref "R234") (pin "1") (pinfunction "1_1") (pintype "passive"))
      (node (ref "R292") (pin "1") (pinfunction "1_1") (pintype "passive"))
      (node (ref "R293") (pin "1") (pinfunction "1_1") (pintype "passive"))
      (node (ref "R303") (pin "1") (pinfunction "1_1") (pintype "passive"))
      (node (ref "R304") (pin "1") (pinfunction "1_1") (pintype "passive"))
      (node (ref "R305") (pin "1") (pinfunction "1_1") (pintype "passive"))
      (node (ref "R322") (pin "1") (pinfunction "1_1") (pintype "passive"))
      (node (ref "U38") (pin "41") (pinfunction "E-PAD_41") (pintype "power_in"))
      (node (ref "U59") (pin "3") (pinfunction "GND_3") (pintype "passive"))
      (node (ref "U59") (pin "8") (pinfunction "GND_8") (pintype "passive"))
      (node (ref "U60") (pin "3") (pinfunction "GND_3") (pintype "passive"))
      (node (ref "U60") (pin "8") (pinfunction "GND_8") (pintype "passive"))
      (node (ref "X4") (pin "2") (pinfunction "2_2") (pintype "passive"))
      (node (ref "X4") (pin "4") (pinfunction "4_4") (pintype "passive"))
    )
    (net (code "38") (name "Net-(C222-Pad2)") (class "Default")
      (node (ref "C222") (pin "2") (pinfunction "2_2") (pintype "passive"))
      (node (ref "R182") (pin "1") (pinfunction "1_1") (pintype "passive"))
      (node (ref "X4") (pin "1") (pinfunction "1_1") (pintype "passive"))
    )
    (net (code "39") (name "Net-(C223-Pad2)") (class "Default")
      (node (ref "C223") (pin "2") (pinfunction "2_2") (pintype "passive"))
      (node (ref "R188") (pin "1") (pinfunction "1_1") (pintype "passive"))
      (node (ref "X4") (pin "3") (pinfunction "3_3") (pintype "passive"))
    )
    (net (code "40") (name "Net-(CN16-CT1)") (class "Default")
      (node (ref "C152") (pin "2") (pinfunction "2_2") (pintype "passive"))
      (node (ref "CN16") (pin "5") (pinfunction "CT1_5") (pintype "passive"))
      (node (ref "CN16") (pin "6") (pinfunction "CT2_6") (pintype "passive"))
    )
    (net (code "41") (name "Net-(CN16-GA)") (class "Default")
      (node (ref "CN16") (pin "11") (pinfunction "GA_11") (pintype "passive"))
      (node (ref "R233") (pin "1") (pinfunction "1_1") (pintype "passive"))
    )
    (net (code "42") (name "Net-(CN16-GC)") (class "Default")
      (node (ref "CN16") (pin "12") (pinfunction "GC_12") (pintype "passive"))
      (node (ref "R319") (pin "2") (pinfunction "2_2") (pintype "passive"))
      (node (ref "U38") (pin "32") (pinfunction "LED0_CFG_EXT_32") (pintype "bidirectional"))
    )
    (net (code "43") (name "Net-(CN16-YA)") (class "Default")
      (node (ref "CN16") (pin "13") (pinfunction "YA_13") (pintype "passive"))
      (node (ref "R322") (pin "2") (pinfunction "2_2") (pintype "passive"))
      (node (ref "U38") (pin "33") (pinfunction "LED1_CFG_LD0_33") (pintype "bidirectional"))
    )
    (net (code "44") (name "Net-(CN16-YC)") (class "Default")
      (node (ref "CN16") (pin "14") (pinfunction "YC_14") (pintype "passive"))
      (node (ref "R234") (pin "2") (pinfunction "2_2") (pintype "passive"))
    )
    (net (code "45") (name "Net-(LD2-Pad2)") (class "Default")
      (node (ref "LD2") (pin "2") (pintype "passive"))
      (node (ref "R151") (pin "1") (pinfunction "1_1") (pintype "passive"))
    )
    (net (code "46") (name "Net-(U38-CLKOUT)") (class "Default")
      (node (ref "R176") (pin "2") (pinfunction "2_2") (pintype "passive"))
      (node (ref "U38") (pin "35") (pinfunction "CLKOUT_35") (pintype "output"))
    )
    (net (code "47") (name "Net-(U38-LED2_CFG_LDO1)") (class "Default")
      (node (ref "LD2") (pin "1") (pintype "passive"))
      (node (ref "R158") (pin "2") (pinfunction "2_2") (pintype "passive"))
      (node (ref "U38") (pin "34") (pinfunction "LED2_CFG_LDO1_34") (pintype "output"))
    )
    (net (code "48") (name "Net-(U38-REG_OUT)") (class "Default")
      (node (ref "LE1") (pin "1") (pinfunction "1_1") (pintype "passive"))
      (node (ref "U38") (pin "30") (pinfunction "REG_OUT_30") (pintype "output"))
    )
    (net (code "49") (name "Net-(U38-RSET)") (class "Default")
      (node (ref "R199") (pin "1") (pinfunction "1_1") (pintype "passive"))
      (node (ref "U38") (pin "39") (pinfunction "RSET_39") (pintype "output"))
    )
    (net (code "50") (name "Net-(U38-RXCLK_PHYAD1)") (class "Default")
      (node (ref "R149") (pin "2") (pinfunction "2_2") (pintype "passive"))
      (node (ref "U38") (pin "27") (pinfunction "RXCLK_PHYAD1_27") (pintype "passive"))
    )
    (net (code "51") (name "Net-(U38-RXCTL_PHYAD2)") (class "Default")
      (node (ref "R150") (pin "2") (pinfunction "2_2") (pintype "passive"))
      (node (ref "U38") (pin "26") (pinfunction "RXCTL_PHYAD2_26") (pintype "passive"))
    )
    (net (code "52") (name "Net-(U38-RXD0_RXDLY)") (class "Default")
      (node (ref "R120") (pin "2") (pinfunction "2_2") (pintype "passive"))
      (node (ref "U38") (pin "25") (pinfunction "RXD0_RXDLY_25") (pintype "output"))
    )
    (net (code "53") (name "Net-(U38-RXD1_TXDLY)") (class "Default")
      (node (ref "R121") (pin "2") (pinfunction "2_2") (pintype "passive"))
      (node (ref "U38") (pin "24") (pinfunction "RXD1_TXDLY_24") (pintype "output"))
    )
    (net (code "54") (name "Net-(U38-RXD2_PLLOFF)") (class "Default")
      (node (ref "R147") (pin "2") (pinfunction "2_2") (pintype "passive"))
      (node (ref "U38") (pin "23") (pinfunction "RXD2_PLLOFF_23") (pintype "output"))
    )
    (net (code "55") (name "Net-(U38-RXD3_PHYAD0)") (class "Default")
      (node (ref "R148") (pin "2") (pinfunction "2_2") (pintype "passive"))
      (node (ref "U38") (pin "22") (pinfunction "RXD3_PHYAD0_22") (pintype "output"))
    )
    (net (code "56") (name "Net-(U38-TXCLK)") (class "Default")
      (node (ref "R161") (pin "2") (pinfunction "2_2") (pintype "passive"))
      (node (ref "U38") (pin "20") (pinfunction "TXCLK_20") (pintype "input"))
    )
    (net (code "57") (name "Net-(U38-TXCTL)") (class "Default")
      (node (ref "R164") (pin "2") (pinfunction "2_2") (pintype "passive"))
      (node (ref "U38") (pin "19") (pinfunction "TXCTL_19") (pintype "input"))
    )
    (net (code "58") (name "Net-(U38-TXD0)") (class "Default")
      (node (ref "R167") (pin "2") (pinfunction "2_2") (pintype "passive"))
      (node (ref "U38") (pin "18") (pinfunction "TXD0_18") (pintype "input"))
    )
    (net (code "59") (name "Net-(U38-TXD1)") (class "Default")
      (node (ref "R173") (pin "2") (pinfunction "2_2") (pintype "passive"))
      (node (ref "U38") (pin "17") (pinfunction "TXD1_17") (pintype "input"))
    )
    (net (code "60") (name "Net-(U38-TXD2)") (class "Default")
      (node (ref "R178") (pin "2") (pinfunction "2_2") (pintype "passive"))
      (node (ref "U38") (pin "16") (pinfunction "TXD2_16") (pintype "input"))
    )
    (net (code "61") (name "Net-(U38-TXD3)") (class "Default")
      (node (ref "R185") (pin "2") (pinfunction "2_2") (pintype "passive"))
      (node (ref "U38") (pin "15") (pinfunction "TXD3_15") (pintype "input"))
    )
    (net (code "62") (name "Net-(U38-XTAL_IN)") (class "Default")
      (node (ref "R182") (pin "2") (pinfunction "2_2") (pintype "passive"))
      (node (ref "U38") (pin "36") (pinfunction "XTAL_IN_36") (pintype "input"))
    )
    (net (code "63") (name "Net-(U38-XTAL_OUT_EXT_CLK)") (class "Default")
      (node (ref "R188") (pin "2") (pinfunction "2_2") (pintype "passive"))
      (node (ref "R196") (pin "2") (pinfunction "2_2") (pintype "passive"))
      (node (ref "U38") (pin "37") (pinfunction "XTAL_OUT_EXT_CLK_37") (pintype "output"))
    )
  )
)
